# TC264D.net
KiCad netlist of a schematic drawn in EasyEDA Pro
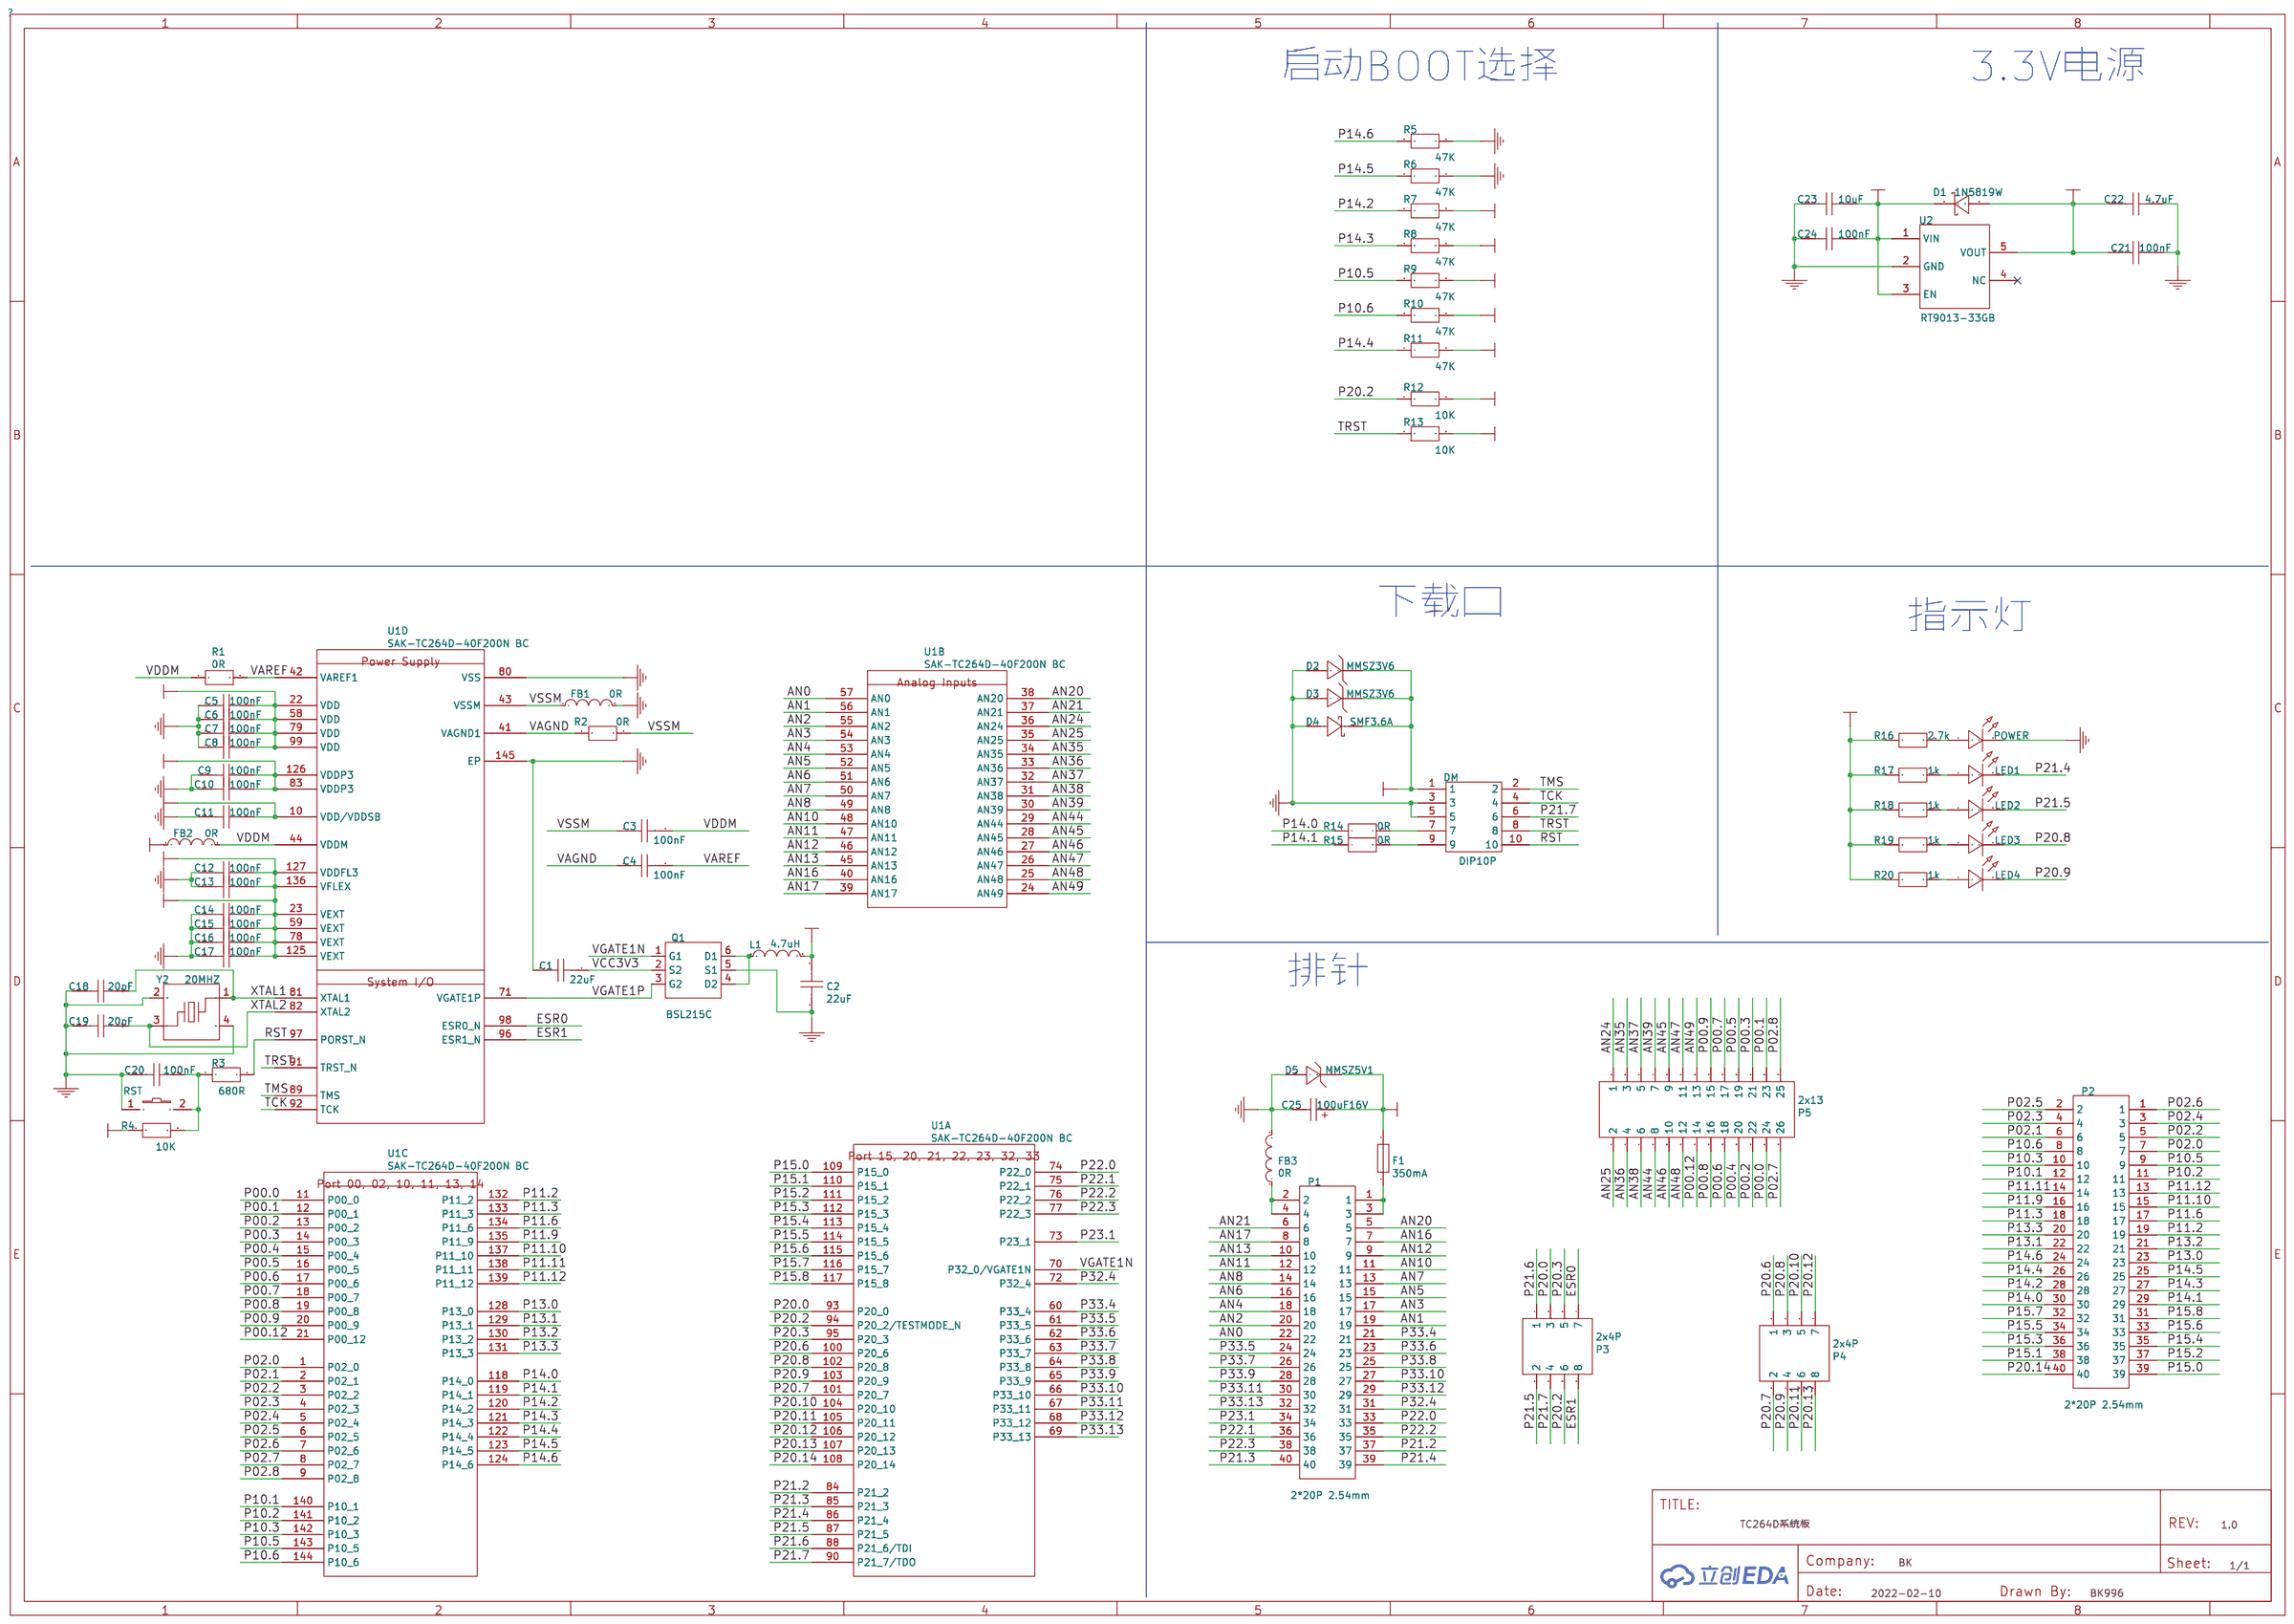
[diagram p0: schematic sheet]

(export (version "E")
  (design (tool "Eeschema 10.0.6"))
  (components
    (comp (ref "C1")
      (value "22uF")
      (footprint "easyedapro:C0603")
      (libsource (lib "easyedapro") (part "22uF"))
    )
    (comp (ref "C2")
      (value "22uF")
      (footprint "easyedapro:C0603")
      (libsource (lib "easyedapro") (part "22uF"))
    )
    (comp (ref "C3")
      (value "100nF")
      (footprint "easyedapro:C0603")
      (libsource (lib "easyedapro") (part "100nF"))
    )
    (comp (ref "C4")
      (value "100nF")
      (footprint "easyedapro:C0603")
      (libsource (lib "easyedapro") (part "100nF"))
    )
    (comp (ref "C5")
      (value "100nF")
      (footprint "easyedapro:C0603")
      (libsource (lib "easyedapro") (part "100nF"))
    )
    (comp (ref "C6")
      (value "100nF")
      (footprint "easyedapro:C0603")
      (libsource (lib "easyedapro") (part "100nF"))
    )
    (comp (ref "C7")
      (value "100nF")
      (footprint "easyedapro:C0603")
      (libsource (lib "easyedapro") (part "100nF"))
    )
    (comp (ref "C8")
      (value "100nF")
      (footprint "easyedapro:C0603")
      (libsource (lib "easyedapro") (part "100nF"))
    )
    (comp (ref "C9")
      (value "100nF")
      (footprint "easyedapro:C0603")
      (libsource (lib "easyedapro") (part "100nF"))
    )
    (comp (ref "C10")
      (value "100nF")
      (footprint "easyedapro:C0603")
      (libsource (lib "easyedapro") (part "100nF"))
    )
    (comp (ref "C11")
      (value "100nF")
      (footprint "easyedapro:C0603")
      (libsource (lib "easyedapro") (part "100nF"))
    )
    (comp (ref "C12")
      (value "100nF")
      (footprint "easyedapro:C0603")
      (libsource (lib "easyedapro") (part "100nF"))
    )
    (comp (ref "C13")
      (value "100nF")
      (footprint "easyedapro:C0603")
      (libsource (lib "easyedapro") (part "100nF"))
    )
    (comp (ref "C14")
      (value "100nF")
      (footprint "easyedapro:C0603")
      (libsource (lib "easyedapro") (part "100nF"))
    )
    (comp (ref "C15")
      (value "100nF")
      (footprint "easyedapro:C0603")
      (libsource (lib "easyedapro") (part "100nF"))
    )
    (comp (ref "C16")
      (value "100nF")
      (footprint "easyedapro:C0603")
      (libsource (lib "easyedapro") (part "100nF"))
    )
    (comp (ref "C17")
      (value "100nF")
      (footprint "easyedapro:C0603")
      (libsource (lib "easyedapro") (part "100nF"))
    )
    (comp (ref "C18")
      (value "20pF")
      (footprint "easyedapro:C0603")
      (libsource (lib "easyedapro") (part "20pF"))
    )
    (comp (ref "C19")
      (value "20pF")
      (footprint "easyedapro:C0603")
      (libsource (lib "easyedapro") (part "20pF"))
    )
    (comp (ref "C20")
      (value "100nF")
      (footprint "easyedapro:C0603")
      (libsource (lib "easyedapro") (part "100nF"))
    )
    (comp (ref "C21")
      (value "100nF")
      (footprint "easyedapro:C0603")
      (libsource (lib "easyedapro") (part "100nF"))
    )
    (comp (ref "C22")
      (value "4.7uF")
      (footprint "easyedapro:C0603")
      (libsource (lib "easyedapro") (part "4.7uF"))
    )
    (comp (ref "C23")
      (value "10uF")
      (footprint "easyedapro:C0603")
      (libsource (lib "easyedapro") (part "10uF"))
    )
    (comp (ref "C24")
      (value "100nF")
      (footprint "easyedapro:C0603")
      (libsource (lib "easyedapro") (part "100nF"))
    )
    (comp (ref "C25")
      (value "100uF16V")
      (footprint "easyedapro:CAP-SMD_L7.3-W4.3-R-RD")
      (fields (field (name "Manufacturer Part") "CA45-D-16V-100UF-K") (field (name "Manufacturer") "CEC"))
      (libsource (lib "easyedapro") (part "100uF16V"))
    )
    (comp (ref "D1")
      (value "1N5819W")
      (footprint "easyedapro:SOD-123F_L2.8-W1.8-LS3.7-RD")
      (fields (field (name "Manufacturer") "Shandong Jingdao Microelectronics"))
      (libsource (lib "easyedapro") (part "1N5819W"))
    )
    (comp (ref "D2")
      (value "MMSZ3V6")
      (footprint "easyedapro:SOD-123_L2.6-W1.6-LS3.5-RD")
      (fields (field (name "Manufacturer Part") "MMSZ3V6CW") (field (name "Manufacturer") "Tak Cheong"))
      (libsource (lib "easyedapro") (part "MMSZ3V6"))
    )
    (comp (ref "D3")
      (value "MMSZ3V6")
      (footprint "easyedapro:SOD-123_L2.6-W1.6-LS3.5-RD")
      (fields (field (name "Manufacturer Part") "MMSZ3V6CW") (field (name "Manufacturer") "Tak Cheong"))
      (libsource (lib "easyedapro") (part "MMSZ3V6"))
    )
    (comp (ref "D4")
      (value "SMF3.6A")
      (footprint "easyedapro:SMF_L2.8-W1.8-LS3.7-FD-1")
      (fields (field (name "Manufacturer Part") "SMF8V5A-E3-18") (field (name "Manufacturer") "VISHAY(威世)"))
      (libsource (lib "easyedapro") (part "SMF3.6A"))
    )
    (comp (ref "D5")
      (value "MMSZ5V1")
      (footprint "easyedapro:SOD-123_L2.7-W1.6-LS3.7-RD")
      (fields (field (name "Manufacturer Part") "MMSZ5V1T1G") (field (name "Manufacturer") "ON Semicon"))
      (libsource (lib "easyedapro") (part "MMSZ5V1"))
    )
    (comp (ref "DM")
      (value "DIP10P")
      (footprint "easyedapro:DIP-2X5P-2.54MM-JN")
      (fields (field (name "Manufacturer Part") "Z-2310118161010") (field (name "Manufacturer") "ZHENGLING"))
      (libsource (lib "easyedapro") (part "DIP10P"))
    )
    (comp (ref "F1")
      (value "350mA")
      (footprint "easyedapro:F1206")
      (fields
        (field (name "Manufacturer Part") "FSMD012-1206-R")
        (field (name "Manufacturer") "Fuzetec Tech")
      )
      (libsource (lib "easyedapro") (part "350mA"))
    )
    (comp (ref "FB1")
      (value "0R")
      (footprint "easyedapro:FB0603")
      (fields (field (name "Manufacturer Part") "PZ2012U121-1R0TF") (field (name "Manufacturer") "Sunlord"))
      (libsource (lib "easyedapro") (part "0R"))
    )
    (comp (ref "FB2")
      (value "0R")
      (footprint "easyedapro:FB0603")
      (fields (field (name "Manufacturer Part") "PZ2012U121-1R0TF") (field (name "Manufacturer") "Sunlord"))
      (libsource (lib "easyedapro") (part "0R"))
    )
    (comp (ref "FB3")
      (value "0R")
      (footprint "easyedapro:FB0603")
      (fields (field (name "Manufacturer Part") "PZ2012U121-1R0TF") (field (name "Manufacturer") "Sunlord"))
      (libsource (lib "easyedapro") (part "0R"))
    )
    (comp (ref "L1")
      (value "4.7uH")
      (footprint "easyedapro:IND-SMD_L7.3-W6.6_MHCI06030")
      (fields (field (name "Manufacturer Part") "MHCI06030-4R7M-R8") (field (name "Manufacturer") "Chilisin"))
      (libsource (lib "easyedapro") (part "4.7uH"))
    )
    (comp (ref "LED1")
      (value "LED-0603_G")
      (footprint "easyedapro:LED0603_GREEN")
      (fields
        (field (name "Manufacturer Part") "19-217/GHC-YR1S2/3T")
        (field (name "Manufacturer") "EVERLIGHT(台湾亿光)")
      )
      (libsource (lib "easyedapro") (part "LED-0603_G"))
    )
    (comp (ref "LED2")
      (value "LED-0603_G")
      (footprint "easyedapro:LED0603_GREEN")
      (fields
        (field (name "Manufacturer Part") "19-217/GHC-YR1S2/3T")
        (field (name "Manufacturer") "EVERLIGHT(台湾亿光)")
      )
      (libsource (lib "easyedapro") (part "LED-0603_G"))
    )
    (comp (ref "LED3")
      (value "LED-0603_G")
      (footprint "easyedapro:LED0603_GREEN")
      (fields
        (field (name "Manufacturer Part") "19-217/GHC-YR1S2/3T")
        (field (name "Manufacturer") "EVERLIGHT(台湾亿光)")
      )
      (libsource (lib "easyedapro") (part "LED-0603_G"))
    )
    (comp (ref "LED4")
      (value "LED-0603_G")
      (footprint "easyedapro:LED0603_GREEN")
      (fields
        (field (name "Manufacturer Part") "19-217/GHC-YR1S2/3T")
        (field (name "Manufacturer") "EVERLIGHT(台湾亿光)")
      )
      (libsource (lib "easyedapro") (part "LED-0603_G"))
    )
    (comp (ref "P1")
      (value "2*20P 2.54mm")
      (footprint "easyedapro:HDR-TH_40P-P2.54-V-F-R2-C20-S2.54")
      (fields (field (name "Manufacturer") "Shenzhen Cankemeng"))
      (libsource (lib "easyedapro") (part "2*20P 2.54mm"))
    )
    (comp (ref "P2")
      (value "2*20P 2.54mm")
      (footprint "easyedapro:HDR-TH_40P-P2.54-V-F-R2-C20-S2.54")
      (fields (field (name "Manufacturer") "Shenzhen Cankemeng"))
      (libsource (lib "easyedapro") (part "2*20P 2.54mm"))
    )
    (comp (ref "P3")
      (value "2x4P")
      (footprint "easyedapro:HDR-TH_8P-P2.54-V-M-R2-C4-S2.54")
      (fields (field (name "Manufacturer Part") "Header2X4P 2.54mm") (field (name "Manufacturer") "ReliaPro"))
      (libsource (lib "easyedapro") (part "2x4P"))
    )
    (comp (ref "P4")
      (value "2x4P")
      (footprint "easyedapro:HDR-TH_8P-P2.54-V-M-R2-C4-S2.54")
      (fields (field (name "Manufacturer Part") "Header2X4P 2.54mm") (field (name "Manufacturer") "ReliaPro"))
      (libsource (lib "easyedapro") (part "2x4P"))
    )
    (comp (ref "P5")
      (value "2x13")
      (footprint "easyedapro:HDR-TH_26P-P2.54-V-F-R2-C13-S2.54-1")
      (fields
        (field (name "Manufacturer Part") "2×13Female header Straight line")
        (field (name "Manufacturer") "BOOMELE")
      )
      (libsource (lib "easyedapro") (part "2x13"))
    )
    (comp (ref "POWER")
      (value "LED-0603_R")
      (footprint "easyedapro:LED0603_RED")
      (fields
        (field (name "Manufacturer Part") "19-217/R6C-AL1M2VY/3T")
        (field (name "Manufacturer") "EVERLIGHT(台湾亿光)")
      )
      (libsource (lib "easyedapro") (part "LED-0603_R"))
    )
    (comp (ref "Q1")
      (value "BSL215C")
      (footprint "easyedapro:TSOP-6_L3.0-W1.5-P0.95-LS2.8-BL")
      (fields (field (name "Manufacturer Part") "BSL215CH6327XTSA1") (field (name "Manufacturer") "Infineon"))
      (libsource (lib "easyedapro") (part "BSL215C"))
    )
    (comp (ref "R1") (value "0R") (footprint "easyedapro:R0805") (libsource (lib "") (part "0R_1")))
    (comp (ref "R2") (value "0R") (footprint "easyedapro:R0805") (libsource (lib "") (part "0R_1")))
    (comp (ref "R3")
      (value "680R")
      (footprint "easyedapro:R0603")
      (libsource (lib "easyedapro") (part "680R"))
    )
    (comp (ref "R4") (value "10K") (footprint "easyedapro:R0603") (libsource (lib "easyedapro") (part "10K")))
    (comp (ref "R5") (value "47K") (footprint "easyedapro:R0603") (libsource (lib "easyedapro") (part "47K")))
    (comp (ref "R6") (value "47K") (footprint "easyedapro:R0603") (libsource (lib "easyedapro") (part "47K")))
    (comp (ref "R7") (value "47K") (footprint "easyedapro:R0603") (libsource (lib "easyedapro") (part "47K")))
    (comp (ref "R8") (value "47K") (footprint "easyedapro:R0603") (libsource (lib "easyedapro") (part "47K")))
    (comp (ref "R9") (value "47K") (footprint "easyedapro:R0603") (libsource (lib "easyedapro") (part "47K")))
    (comp (ref "R10")
      (value "47K")
      (footprint "easyedapro:R0603")
      (libsource (lib "easyedapro") (part "47K"))
    )
    (comp (ref "R11")
      (value "47K")
      (footprint "easyedapro:R0603")
      (libsource (lib "easyedapro") (part "47K"))
    )
    (comp (ref "R12")
      (value "10K")
      (footprint "easyedapro:R0603")
      (libsource (lib "easyedapro") (part "10K"))
    )
    (comp (ref "R13")
      (value "10K")
      (footprint "easyedapro:R0603")
      (libsource (lib "easyedapro") (part "10K"))
    )
    (comp (ref "R14") (value "0R") (footprint "easyedapro:R0805") (libsource (lib "") (part "0R_1")))
    (comp (ref "R15") (value "0R") (footprint "easyedapro:R0805") (libsource (lib "") (part "0R_1")))
    (comp (ref "R16")
      (value "2.7k")
      (footprint "easyedapro:R0603")
      (libsource (lib "easyedapro") (part "2.7k"))
    )
    (comp (ref "R17") (value "1k") (footprint "easyedapro:R0603") (libsource (lib "easyedapro") (part "1k")))
    (comp (ref "R18") (value "1k") (footprint "easyedapro:R0603") (libsource (lib "easyedapro") (part "1k")))
    (comp (ref "R19") (value "1k") (footprint "easyedapro:R0603") (libsource (lib "easyedapro") (part "1k")))
    (comp (ref "R20") (value "1k") (footprint "easyedapro:R0603") (libsource (lib "easyedapro") (part "1k")))
    (comp (ref "RST")
      (value "K2-3.6×6.1_SMD")
      (footprint "easyedapro:3*6*2.5MM轻触开关")
      (fields (field (name "Manufacturer Part") "K2-1107ST-A4SW-06"))
      (libsource (lib "easyedapro") (part "K2-3.6×6.1_SMD"))
    )
    (comp (ref "U1")
      (value "SAK-TC264D-40F200N BC")
      (footprint "easyedapro:QFP50P2200X2200X160-145N-1")
      (fields (field (name "Manufacturer") "Infineon Technologies"))
      (libsource (lib "easyedapro") (part "SAK-TC264D-40F200N BC"))
    )
    (comp (ref "U2")
      (value "RT9013-33GB")
      (footprint "easyedapro:SOT-23-5_L3.0-W1.7-P0.95-LS2.8-BR")
      (fields (field (name "Manufacturer") "RICHTEK"))
      (libsource (lib "easyedapro") (part "RT9013-33GB"))
    )
    (comp (ref "Y2")
      (value "20MHZ")
      (footprint "easyedapro:CRYSTAL-SMD_4P-L3.2-W2.5-BL")
      (fields (field (name "Manufacturer Part") "smd-3225-8Mhz"))
      (libsource (lib "easyedapro") (part "20MHZ"))
    )
  )
  (nets
    (net (code "1") (name "/AN0") (class "Default")
      (node (ref "P1") (pin "22") (pinfunction "22_22") (pintype "unspecified"))
      (node (ref "U1") (pin "57") (pinfunction "AN0_57") (pintype "input"))
    )
    (net (code "2") (name "/AN1") (class "Default")
      (node (ref "P1") (pin "19") (pinfunction "19_19") (pintype "unspecified"))
      (node (ref "U1") (pin "56") (pinfunction "AN1_56") (pintype "input"))
    )
    (net (code "3") (name "/AN2") (class "Default")
      (node (ref "P1") (pin "20") (pinfunction "20_20") (pintype "unspecified"))
      (node (ref "U1") (pin "55") (pinfunction "AN2_55") (pintype "input"))
    )
    (net (code "4") (name "/AN3") (class "Default")
      (node (ref "P1") (pin "17") (pinfunction "17_17") (pintype "unspecified"))
      (node (ref "U1") (pin "54") (pinfunction "AN3_54") (pintype "input"))
    )
    (net (code "5") (name "/AN4") (class "Default")
      (node (ref "P1") (pin "18") (pinfunction "18_18") (pintype "unspecified"))
      (node (ref "U1") (pin "53") (pinfunction "AN4_53") (pintype "input"))
    )
    (net (code "6") (name "/AN5") (class "Default")
      (node (ref "P1") (pin "15") (pinfunction "15_15") (pintype "unspecified"))
      (node (ref "U1") (pin "52") (pinfunction "AN5_52") (pintype "input"))
    )
    (net (code "7") (name "/AN6") (class "Default")
      (node (ref "P1") (pin "16") (pinfunction "16_16") (pintype "unspecified"))
      (node (ref "U1") (pin "51") (pinfunction "AN6_51") (pintype "input"))
    )
    (net (code "8") (name "/AN7") (class "Default")
      (node (ref "P1") (pin "13") (pinfunction "13_13") (pintype "unspecified"))
      (node (ref "U1") (pin "50") (pinfunction "AN7_50") (pintype "input"))
    )
    (net (code "9") (name "/AN8") (class "Default")
      (node (ref "P1") (pin "14") (pinfunction "14_14") (pintype "unspecified"))
      (node (ref "U1") (pin "49") (pinfunction "AN8_49") (pintype "input"))
    )
    (net (code "10") (name "/AN10") (class "Default")
      (node (ref "P1") (pin "11") (pinfunction "11_11") (pintype "unspecified"))
      (node (ref "U1") (pin "48") (pinfunction "AN10_48") (pintype "input"))
    )
    (net (code "11") (name "/AN11") (class "Default")
      (node (ref "P1") (pin "12") (pinfunction "12_12") (pintype "unspecified"))
      (node (ref "U1") (pin "47") (pinfunction "AN11_47") (pintype "input"))
    )
    (net (code "12") (name "/AN12") (class "Default")
      (node (ref "P1") (pin "9") (pinfunction "9_9") (pintype "unspecified"))
      (node (ref "U1") (pin "46") (pinfunction "AN12_46") (pintype "input"))
    )
    (net (code "13") (name "/AN13") (class "Default")
      (node (ref "P1") (pin "10") (pinfunction "10_10") (pintype "unspecified"))
      (node (ref "U1") (pin "45") (pinfunction "AN13_45") (pintype "input"))
    )
    (net (code "14") (name "/AN16") (class "Default")
      (node (ref "P1") (pin "7") (pinfunction "7_7") (pintype "unspecified"))
      (node (ref "U1") (pin "40") (pinfunction "AN16_40") (pintype "input"))
    )
    (net (code "15") (name "/AN17") (class "Default")
      (node (ref "P1") (pin "8") (pinfunction "8_8") (pintype "unspecified"))
      (node (ref "U1") (pin "39") (pinfunction "AN17_39") (pintype "input"))
    )
    (net (code "16") (name "/AN20") (class "Default")
      (node (ref "P1") (pin "5") (pinfunction "5_5") (pintype "unspecified"))
      (node (ref "U1") (pin "38") (pinfunction "AN20_38") (pintype "input"))
    )
    (net (code "17") (name "/AN21") (class "Default")
      (node (ref "P1") (pin "6") (pinfunction "6_6") (pintype "unspecified"))
      (node (ref "U1") (pin "37") (pinfunction "AN21_37") (pintype "input"))
    )
    (net (code "18") (name "/AN24") (class "Default")
      (node (ref "P5") (pin "1") (pinfunction "1_1") (pintype "input"))
      (node (ref "U1") (pin "36") (pinfunction "AN24_36") (pintype "input"))
    )
    (net (code "19") (name "/AN25") (class "Default")
      (node (ref "P5") (pin "2") (pinfunction "2_2") (pintype "input"))
      (node (ref "U1") (pin "35") (pinfunction "AN25_35") (pintype "input"))
    )
    (net (code "20") (name "/AN35") (class "Default")
      (node (ref "P5") (pin "3") (pinfunction "3_3") (pintype "input"))
      (node (ref "U1") (pin "34") (pinfunction "AN35_34") (pintype "input"))
    )
    (net (code "21") (name "/AN36") (class "Default")
      (node (ref "P5") (pin "4") (pinfunction "4_4") (pintype "input"))
      (node (ref "U1") (pin "33") (pinfunction "AN36_33") (pintype "input"))
    )
    (net (code "22") (name "/AN37") (class "Default")
      (node (ref "P5") (pin "5") (pinfunction "5_5") (pintype "input"))
      (node (ref "U1") (pin "32") (pinfunction "AN37_32") (pintype "input"))
    )
    (net (code "23") (name "/AN38") (class "Default")
      (node (ref "P5") (pin "6") (pinfunction "6_6") (pintype "input"))
      (node (ref "U1") (pin "31") (pinfunction "AN38_31") (pintype "input"))
    )
    (net (code "24") (name "/AN39") (class "Default")
      (node (ref "P5") (pin "7") (pinfunction "7_7") (pintype "input"))
      (node (ref "U1") (pin "30") (pinfunction "AN39_30") (pintype "input"))
    )
    (net (code "25") (name "/AN44") (class "Default")
      (node (ref "P5") (pin "8") (pinfunction "8_8") (pintype "input"))
      (node (ref "U1") (pin "29") (pinfunction "AN44_29") (pintype "input"))
    )
    (net (code "26") (name "/AN45") (class "Default")
      (node (ref "P5") (pin "9") (pinfunction "9_9") (pintype "input"))
      (node (ref "U1") (pin "28") (pinfunction "AN45_28") (pintype "input"))
    )
    (net (code "27") (name "/AN46") (class "Default")
      (node (ref "P5") (pin "10") (pinfunction "10_10") (pintype "input"))
      (node (ref "U1") (pin "27") (pinfunction "AN46_27") (pintype "input"))
    )
    (net (code "28") (name "/AN47") (class "Default")
      (node (ref "P5") (pin "11") (pinfunction "11_11") (pintype "input"))
      (node (ref "U1") (pin "26") (pinfunction "AN47_26") (pintype "input"))
    )
    (net (code "29") (name "/AN48") (class "Default")
      (node (ref "P5") (pin "12") (pinfunction "12_12") (pintype "input"))
      (node (ref "U1") (pin "25") (pinfunction "AN48_25") (pintype "input"))
    )
    (net (code "30") (name "/AN49") (class "Default")
      (node (ref "P5") (pin "13") (pinfunction "13_13") (pintype "input"))
      (node (ref "U1") (pin "24") (pinfunction "AN49_24") (pintype "input"))
    )
    (net (code "31") (name "/ESR0") (class "Default")
      (node (ref "P3") (pin "7") (pinfunction "7_7") (pintype "input"))
      (node (ref "U1") (pin "98") (pinfunction "ESR0_N_98") (pintype "bidirectional"))
    )
    (net (code "32") (name "/ESR1") (class "Default")
      (node (ref "P3") (pin "8") (pinfunction "8_8") (pintype "input"))
      (node (ref "U1") (pin "96") (pinfunction "ESR1_N_96") (pintype "bidirectional"))
    )
    (net (code "33") (name "/P00.0") (class "Default")
      (node (ref "P5") (pin "24") (pinfunction "24_24") (pintype "input"))
      (node (ref "U1") (pin "11") (pinfunction "P00_0_11") (pintype "bidirectional"))
    )
    (net (code "34") (name "/P00.1") (class "Default")
      (node (ref "P5") (pin "23") (pinfunction "23_23") (pintype "input"))
      (node (ref "U1") (pin "12") (pinfunction "P00_1_12") (pintype "bidirectional"))
    )
    (net (code "35") (name "/P00.2") (class "Default")
      (node (ref "P5") (pin "22") (pinfunction "22_22") (pintype "input"))
      (node (ref "U1") (pin "13") (pinfunction "P00_2_13") (pintype "bidirectional"))
    )
    (net (code "36") (name "/P00.3") (class "Default")
      (node (ref "P5") (pin "21") (pinfunction "21_21") (pintype "input"))
      (node (ref "U1") (pin "14") (pinfunction "P00_3_14") (pintype "bidirectional"))
    )
    (net (code "37") (name "/P00.4") (class "Default")
      (node (ref "P5") (pin "20") (pinfunction "20_20") (pintype "input"))
      (node (ref "U1") (pin "15") (pinfunction "P00_4_15") (pintype "bidirectional"))
    )
    (net (code "38") (name "/P00.5") (class "Default")
      (node (ref "P5") (pin "19") (pinfunction "19_19") (pintype "input"))
      (node (ref "U1") (pin "16") (pinfunction "P00_5_16") (pintype "bidirectional"))
    )
    (net (code "39") (name "/P00.6") (class "Default")
      (node (ref "P5") (pin "18") (pinfunction "18_18") (pintype "input"))
      (node (ref "U1") (pin "17") (pinfunction "P00_6_17") (pintype "bidirectional"))
    )
    (net (code "40") (name "/P00.7") (class "Default")
      (node (ref "P5") (pin "17") (pinfunction "17_17") (pintype "input"))
      (node (ref "U1") (pin "18") (pinfunction "P00_7_18") (pintype "bidirectional"))
    )
    (net (code "41") (name "/P00.8") (class "Default")
      (node (ref "P5") (pin "16") (pinfunction "16_16") (pintype "input"))
      (node (ref "U1") (pin "19") (pinfunction "P00_8_19") (pintype "bidirectional"))
    )
    (net (code "42") (name "/P00.9") (class "Default")
      (node (ref "P5") (pin "15") (pinfunction "15_15") (pintype "input"))
      (node (ref "U1") (pin "20") (pinfunction "P00_9_20") (pintype "bidirectional"))
    )
    (net (code "43") (name "/P00.12") (class "Default")
      (node (ref "P5") (pin "14") (pinfunction "14_14") (pintype "input"))
      (node (ref "U1") (pin "21") (pinfunction "P00_12_21") (pintype "bidirectional"))
    )
    (net (code "44") (name "/P02.0") (class "Default")
      (node (ref "P2") (pin "7") (pinfunction "7_7") (pintype "unspecified"))
      (node (ref "U1") (pin "1") (pinfunction "P02_0_1") (pintype "bidirectional"))
    )
    (net (code "45") (name "/P02.1") (class "Default")
      (node (ref "P2") (pin "6") (pinfunction "6_6") (pintype "unspecified"))
      (node (ref "U1") (pin "2") (pinfunction "P02_1_2") (pintype "bidirectional"))
    )
    (net (code "46") (name "/P02.2") (class "Default")
      (node (ref "P2") (pin "5") (pinfunction "5_5") (pintype "unspecified"))
      (node (ref "U1") (pin "3") (pinfunction "P02_2_3") (pintype "bidirectional"))
    )
    (net (code "47") (name "/P02.3") (class "Default")
      (node (ref "P2") (pin "4") (pinfunction "4_4") (pintype "unspecified"))
      (node (ref "U1") (pin "4") (pinfunction "P02_3_4") (pintype "bidirectional"))
    )
    (net (code "48") (name "/P02.4") (class "Default")
      (node (ref "P2") (pin "3") (pinfunction "3_3") (pintype "unspecified"))
      (node (ref "U1") (pin "5") (pinfunction "P02_4_5") (pintype "bidirectional"))
    )
    (net (code "49") (name "/P02.5") (class "Default")
      (node (ref "P2") (pin "2") (pinfunction "2_2") (pintype "unspecified"))
      (node (ref "U1") (pin "6") (pinfunction "P02_5_6") (pintype "bidirectional"))
    )
    (net (code "50") (name "/P02.6") (class "Default")
      (node (ref "P2") (pin "1") (pinfunction "1_1") (pintype "unspecified"))
      (node (ref "U1") (pin "7") (pinfunction "P02_6_7") (pintype "bidirectional"))
    )
    (net (code "51") (name "/P02.7") (class "Default")
      (node (ref "P5") (pin "26") (pinfunction "26_26") (pintype "input"))
      (node (ref "U1") (pin "8") (pinfunction "P02_7_8") (pintype "bidirectional"))
    )
    (net (code "52") (name "/P02.8") (class "Default")
      (node (ref "P5") (pin "25") (pinfunction "25_25") (pintype "input"))
      (node (ref "U1") (pin "9") (pinfunction "P02_8_9") (pintype "bidirectional"))
    )
    (net (code "53") (name "/P10.1") (class "Default")
      (node (ref "P2") (pin "12") (pinfunction "12_12") (pintype "unspecified"))
      (node (ref "U1") (pin "140") (pinfunction "P10_1_140") (pintype "bidirectional"))
    )
    (net (code "54") (name "/P10.2") (class "Default")
      (node (ref "P2") (pin "11") (pinfunction "11_11") (pintype "unspecified"))
      (node (ref "U1") (pin "141") (pinfunction "P10_2_141") (pintype "bidirectional"))
    )
    (net (code "55") (name "/P10.3") (class "Default")
      (node (ref "P2") (pin "10") (pinfunction "10_10") (pintype "unspecified"))
      (node (ref "U1") (pin "142") (pinfunction "P10_3_142") (pintype "bidirectional"))
    )
    (net (code "56") (name "/P10.5") (class "Default")
      (node (ref "P2") (pin "9") (pinfunction "9_9") (pintype "unspecified"))
      (node (ref "R9") (pin "1") (pinfunction "1_1") (pintype "unspecified"))
      (node (ref "U1") (pin "143") (pinfunction "P10_5_143") (pintype "bidirectional"))
    )
    (net (code "57") (name "/P10.6") (class "Default")
      (node (ref "P2") (pin "8") (pinfunction "8_8") (pintype "unspecified"))
      (node (ref "R10") (pin "1") (pinfunction "1_1") (pintype "unspecified"))
      (node (ref "U1") (pin "144") (pinfunction "P10_6_144") (pintype "bidirectional"))
    )
    (net (code "58") (name "/P11.2") (class "Default")
      (node (ref "P2") (pin "19") (pinfunction "19_19") (pintype "unspecified"))
      (node (ref "U1") (pin "132") (pinfunction "P11_2_132") (pintype "bidirectional"))
    )
    (net (code "59") (name "/P11.3") (class "Default")
      (node (ref "P2") (pin "18") (pinfunction "18_18") (pintype "unspecified"))
      (node (ref "U1") (pin "133") (pinfunction "P11_3_133") (pintype "bidirectional"))
    )
    (net (code "60") (name "/P11.6") (class "Default")
      (node (ref "P2") (pin "17") (pinfunction "17_17") (pintype "unspecified"))
      (node (ref "U1") (pin "134") (pinfunction "P11_6_134") (pintype "bidirectional"))
    )
    (net (code "61") (name "/P11.9") (class "Default")
      (node (ref "P2") (pin "16") (pinfunction "16_16") (pintype "unspecified"))
      (node (ref "U1") (pin "135") (pinfunction "P11_9_135") (pintype "bidirectional"))
    )
    (net (code "62") (name "/P11.10") (class "Default")
      (node (ref "P2") (pin "15") (pinfunction "15_15") (pintype "unspecified"))
      (node (ref "U1") (pin "137") (pinfunction "P11_10_137") (pintype "bidirectional"))
    )
    (net (code "63") (name "/P11.11") (class "Default")
      (node (ref "P2") (pin "14") (pinfunction "14_14") (pintype "unspecified"))
      (node (ref "U1") (pin "138") (pinfunction "P11_11_138") (pintype "bidirectional"))
    )
    (net (code "64") (name "/P11.12") (class "Default")
      (node (ref "P2") (pin "13") (pinfunction "13_13") (pintype "unspecified"))
      (node (ref "U1") (pin "139") (pinfunction "P11_12_139") (pintype "bidirectional"))
    )
    (net (code "65") (name "/P13.0") (class "Default")
      (node (ref "P2") (pin "23") (pinfunction "23_23") (pintype "unspecified"))
      (node (ref "U1") (pin "128") (pinfunction "P13_0_128") (pintype "bidirectional"))
    )
    (net (code "66") (name "/P13.1") (class "Default")
      (node (ref "P2") (pin "22") (pinfunction "22_22") (pintype "unspecified"))
      (node (ref "U1") (pin "129") (pinfunction "P13_1_129") (pintype "bidirectional"))
    )
    (net (code "67") (name "/P13.2") (class "Default")
      (node (ref "P2") (pin "21") (pinfunction "21_21") (pintype "unspecified"))
      (node (ref "U1") (pin "130") (pinfunction "P13_2_130") (pintype "bidirectional"))
    )
    (net (code "68") (name "/P13.3") (class "Default")
      (node (ref "P2") (pin "20") (pinfunction "20_20") (pintype "unspecified"))
      (node (ref "U1") (pin "131") (pinfunction "P13_3_131") (pintype "bidirectional"))
    )
    (net (code "69") (name "/P14.0") (class "Default")
      (node (ref "P2") (pin "30") (pinfunction "30_30") (pintype "unspecified"))
      (node (ref "R14") (pin "1") (pinfunction "1_1") (pintype "unspecified"))
      (node (ref "U1") (pin "118") (pinfunction "P14_0_118") (pintype "bidirectional"))
    )
    (net (code "70") (name "/P14.1") (class "Default")
      (node (ref "P2") (pin "29") (pinfunction "29_29") (pintype "unspecified"))
      (node (ref "R15") (pin "1") (pinfunction "1_1") (pintype "unspecified"))
      (node (ref "U1") (pin "119") (pinfunction "P14_1_119") (pintype "bidirectional"))
    )
    (net (code "71") (name "/P14.2") (class "Default")
      (node (ref "P2") (pin "28") (pinfunction "28_28") (pintype "unspecified"))
      (node (ref "R7") (pin "1") (pinfunction "1_1") (pintype "unspecified"))
      (node (ref "U1") (pin "120") (pinfunction "P14_2_120") (pintype "bidirectional"))
    )
    (net (code "72") (name "/P14.3") (class "Default")
      (node (ref "P2") (pin "27") (pinfunction "27_27") (pintype "unspecified"))
      (node (ref "R8") (pin "1") (pinfunction "1_1") (pintype "unspecified"))
      (node (ref "U1") (pin "121") (pinfunction "P14_3_121") (pintype "bidirectional"))
    )
    (net (code "73") (name "/P14.4") (class "Default")
      (node (ref "P2") (pin "26") (pinfunction "26_26") (pintype "unspecified"))
      (node (ref "R11") (pin "1") (pinfunction "1_1") (pintype "unspecified"))
      (node (ref "U1") (pin "122") (pinfunction "P14_4_122") (pintype "bidirectional"))
    )
    (net (code "74") (name "/P14.5") (class "Default")
      (node (ref "P2") (pin "25") (pinfunction "25_25") (pintype "unspecified"))
      (node (ref "R6") (pin "1") (pinfunction "1_1") (pintype "unspecified"))
      (node (ref "U1") (pin "123") (pinfunction "P14_5_123") (pintype "bidirectional"))
    )
    (net (code "75") (name "/P14.6") (class "Default")
      (node (ref "P2") (pin "24") (pinfunction "24_24") (pintype "unspecified"))
      (node (ref "R5") (pin "1") (pinfunction "1_1") (pintype "unspecified"))
      (node (ref "U1") (pin "124") (pinfunction "P14_6_124") (pintype "bidirectional"))
    )
    (net (code "76") (name "/P15.0") (class "Default")
      (node (ref "P2") (pin "39") (pinfunction "39_39") (pintype "unspecified"))
      (node (ref "U1") (pin "109") (pinfunction "P15_0_109") (pintype "bidirectional"))
    )
    (net (code "77") (name "/P15.1") (class "Default")
      (node (ref "P2") (pin "38") (pinfunction "38_38") (pintype "unspecified"))
      (node (ref "U1") (pin "110") (pinfunction "P15_1_110") (pintype "bidirectional"))
    )
    (net (code "78") (name "/P15.2") (class "Default")
      (node (ref "P2") (pin "37") (pinfunction "37_37") (pintype "unspecified"))
      (node (ref "U1") (pin "111") (pinfunction "P15_2_111") (pintype "bidirectional"))
    )
    (net (code "79") (name "/P15.3") (class "Default")
      (node (ref "P2") (pin "36") (pinfunction "36_36") (pintype "unspecified"))
      (node (ref "U1") (pin "112") (pinfunction "P15_3_112") (pintype "bidirectional"))
    )
    (net (code "80") (name "/P15.4") (class "Default")
      (node (ref "P2") (pin "35") (pinfunction "35_35") (pintype "unspecified"))
      (node (ref "U1") (pin "113") (pinfunction "P15_4_113") (pintype "bidirectional"))
    )
    (net (code "81") (name "/P15.5") (class "Default")
      (node (ref "P2") (pin "34") (pinfunction "34_34") (pintype "unspecified"))
      (node (ref "U1") (pin "114") (pinfunction "P15_5_114") (pintype "bidirectional"))
    )
    (net (code "82") (name "/P15.6") (class "Default")
      (node (ref "P2") (pin "33") (pinfunction "33_33") (pintype "unspecified"))
      (node (ref "U1") (pin "115") (pinfunction "P15_6_115") (pintype "bidirectional"))
    )
    (net (code "83") (name "/P15.7") (class "Default")
      (node (ref "P2") (pin "32") (pinfunction "32_32") (pintype "unspecified"))
      (node (ref "U1") (pin "116") (pinfunction "P15_7_116") (pintype "bidirectional"))
    )
    (net (code "84") (name "/P15.8") (class "Default")
      (node (ref "P2") (pin "31") (pinfunction "31_31") (pintype "unspecified"))
      (node (ref "U1") (pin "117") (pinfunction "P15_8_117") (pintype "bidirectional"))
    )
    (net (code "85") (name "/P20.0") (class "Default")
      (node (ref "P3") (pin "3") (pinfunction "3_3") (pintype "input"))
      (node (ref "U1") (pin "93") (pinfunction "P20_0_93") (pintype "bidirectional"))
    )
    (net (code "86") (name "/P20.2") (class "Default")
      (node (ref "P3") (pin "6") (pinfunction "6_6") (pintype "input"))
      (node (ref "R12") (pin "1") (pinfunction "1_1") (pintype "unspecified"))
      (node (ref "U1") (pin "94") (pinfunction "P20_2/TESTMODE_N_94") (pintype "bidirectional"))
    )
    (net (code "87") (name "/P20.3") (class "Default")
      (node (ref "P3") (pin "5") (pinfunction "5_5") (pintype "input"))
      (node (ref "U1") (pin "95") (pinfunction "P20_3_95") (pintype "bidirectional"))
    )
    (net (code "88") (name "/P20.6") (class "Default")
      (node (ref "P4") (pin "1") (pinfunction "1_1") (pintype "input"))
      (node (ref "U1") (pin "100") (pinfunction "P20_6_100") (pintype "bidirectional"))
    )
    (net (code "89") (name "/P20.7") (class "Default")
      (node (ref "P4") (pin "2") (pinfunction "2_2") (pintype "input"))
      (node (ref "U1") (pin "101") (pinfunction "P20_7_101") (pintype "bidirectional"))
    )
    (net (code "90") (name "/P20.8") (class "Default")
      (node (ref "LED3") (pin "2") (pinfunction "2_2") (pintype "unspecified"))
      (node (ref "P4") (pin "3") (pinfunction "3_3") (pintype "input"))
      (node (ref "U1") (pin "102") (pinfunction "P20_8_102") (pintype "bidirectional"))
    )
    (net (code "91") (name "/P20.9") (class "Default")
      (node (ref "LED4") (pin "2") (pinfunction "2_2") (pintype "unspecified"))
      (node (ref "P4") (pin "4") (pinfunction "4_4") (pintype "input"))
      (node (ref "U1") (pin "103") (pinfunction "P20_9_103") (pintype "bidirectional"))
    )
    (net (code "92") (name "/P20.10") (class "Default")
      (node (ref "P4") (pin "5") (pinfunction "5_5") (pintype "input"))
      (node (ref "U1") (pin "104") (pinfunction "P20_10_104") (pintype "bidirectional"))
    )
    (net (code "93") (name "/P20.11") (class "Default")
      (node (ref "P4") (pin "6") (pinfunction "6_6") (pintype "input"))
      (node (ref "U1") (pin "105") (pinfunction "P20_11_105") (pintype "bidirectional"))
    )
    (net (code "94") (name "/P20.12") (class "Default")
      (node (ref "P4") (pin "7") (pinfunction "7_7") (pintype "input"))
      (node (ref "U1") (pin "106") (pinfunction "P20_12_106") (pintype "bidirectional"))
    )
    (net (code "95") (name "/P20.13") (class "Default")
      (node (ref "P4") (pin "8") (pinfunction "8_8") (pintype "input"))
      (node (ref "U1") (pin "107") (pinfunction "P20_13_107") (pintype "bidirectional"))
    )
    (net (code "96") (name "/P20.14") (class "Default")
      (node (ref "P2") (pin "40") (pinfunction "40_40") (pintype "unspecified"))
      (node (ref "U1") (pin "108") (pinfunction "P20_14_108") (pintype "bidirectional"))
    )
    (net (code "97") (name "/P21.2") (class "Default")
      (node (ref "P1") (pin "37") (pinfunction "37_37") (pintype "unspecified"))
      (node (ref "U1") (pin "84") (pinfunction "P21_2_84") (pintype "bidirectional"))
    )
    (net (code "98") (name "/P21.3") (class "Default")
      (node (ref "P1") (pin "40") (pinfunction "40_40") (pintype "unspecified"))
      (node (ref "U1") (pin "85") (pinfunction "P21_3_85") (pintype "bidirectional"))
    )
    (net (code "99") (name "/P21.4") (class "Default")
      (node (ref "LED1") (pin "2") (pinfunction "2_2") (pintype "unspecified"))
      (node (ref "P1") (pin "39") (pinfunction "39_39") (pintype "unspecified"))
      (node (ref "U1") (pin "86") (pinfunction "P21_4_86") (pintype "bidirectional"))
    )
    (net (code "100") (name "/P21.5") (class "Default")
      (node (ref "LED2") (pin "2") (pinfunction "2_2") (pintype "unspecified"))
      (node (ref "P3") (pin "2") (pinfunction "2_2") (pintype "input"))
      (node (ref "U1") (pin "87") (pinfunction "P21_5_87") (pintype "bidirectional"))
    )
    (net (code "101") (name "/P21.6") (class "Default")
      (node (ref "P3") (pin "1") (pinfunction "1_1") (pintype "input"))
      (node (ref "U1") (pin "88") (pinfunction "P21_6/TDI_88") (pintype "bidirectional"))
    )
    (net (code "102") (name "/P21.7") (class "Default")
      (node (ref "DM") (pin "6") (pinfunction "6_6") (pintype "unspecified"))
      (node (ref "P3") (pin "4") (pinfunction "4_4") (pintype "input"))
      (node (ref "U1") (pin "90") (pinfunction "P21_7/TDO_90") (pintype "bidirectional"))
    )
    (net (code "103") (name "/P22.0") (class "Default")
      (node (ref "P1") (pin "33") (pinfunction "33_33") (pintype "unspecified"))
      (node (ref "U1") (pin "74") (pinfunction "P22_0_74") (pintype "bidirectional"))
    )
    (net (code "104") (name "/P22.1") (class "Default")
      (node (ref "P1") (pin "36") (pinfunction "36_36") (pintype "unspecified"))
      (node (ref "U1") (pin "75") (pinfunction "P22_1_75") (pintype "bidirectional"))
    )
    (net (code "105") (name "/P22.2") (class "Default")
      (node (ref "P1") (pin "35") (pinfunction "35_35") (pintype "unspecified"))
      (node (ref "U1") (pin "76") (pinfunction "P22_2_76") (pintype "bidirectional"))
    )
    (net (code "106") (name "/P22.3") (class "Default")
      (node (ref "P1") (pin "38") (pinfunction "38_38") (pintype "unspecified"))
      (node (ref "U1") (pin "77") (pinfunction "P22_3_77") (pintype "bidirectional"))
    )
    (net (code "107") (name "/P23.1") (class "Default")
      (node (ref "P1") (pin "34") (pinfunction "34_34") (pintype "unspecified"))
      (node (ref "U1") (pin "73") (pinfunction "P23_1_73") (pintype "bidirectional"))
    )
    (net (code "108") (name "/P32.4") (class "Default")
      (node (ref "P1") (pin "31") (pinfunction "31_31") (pintype "unspecified"))
      (node (ref "U1") (pin "72") (pinfunction "P32_4_72") (pintype "bidirectional"))
    )
    (net (code "109") (name "/P33.4") (class "Default")
      (node (ref "P1") (pin "21") (pinfunction "21_21") (pintype "unspecified"))
      (node (ref "U1") (pin "60") (pinfunction "P33_4_60") (pintype "bidirectional"))
    )
    (net (code "110") (name "/P33.5") (class "Default")
      (node (ref "P1") (pin "24") (pinfunction "24_24") (pintype "unspecified"))
      (node (ref "U1") (pin "61") (pinfunction "P33_5_61") (pintype "bidirectional"))
    )
    (net (code "111") (name "/P33.6") (class "Default")
      (node (ref "P1") (pin "23") (pinfunction "23_23") (pintype "unspecified"))
      (node (ref "U1") (pin "62") (pinfunction "P33_6_62") (pintype "bidirectional"))
    )
    (net (code "112") (name "/P33.7") (class "Default")
      (node (ref "P1") (pin "26") (pinfunction "26_26") (pintype "unspecified"))
      (node (ref "U1") (pin "63") (pinfunction "P33_7_63") (pintype "bidirectional"))
    )
    (net (code "113") (name "/P33.8") (class "Default")
      (node (ref "P1") (pin "25") (pinfunction "25_25") (pintype "unspecified"))
      (node (ref "U1") (pin "64") (pinfunction "P33_8_64") (pintype "bidirectional"))
    )
    (net (code "114") (name "/P33.9") (class "Default")
      (node (ref "P1") (pin "28") (pinfunction "28_28") (pintype "unspecified"))
      (node (ref "U1") (pin "65") (pinfunction "P33_9_65") (pintype "bidirectional"))
    )
    (net (code "115") (name "/P33.10") (class "Default")
      (node (ref "P1") (pin "27") (pinfunction "27_27") (pintype "unspecified"))
      (node (ref "U1") (pin "66") (pinfunction "P33_10_66") (pintype "bidirectional"))
    )
    (net (code "116") (name "/P33.11") (class "Default")
      (node (ref "P1") (pin "30") (pinfunction "30_30") (pintype "unspecified"))
      (node (ref "U1") (pin "67") (pinfunction "P33_11_67") (pintype "bidirectional"))
    )
    (net (code "117") (name "/P33.12") (class "Default")
      (node (ref "P1") (pin "29") (pinfunction "29_29") (pintype "unspecified"))
      (node (ref "U1") (pin "68") (pinfunction "P33_12_68") (pintype "bidirectional"))
    )
    (net (code "118") (name "/P33.13") (class "Default")
      (node (ref "P1") (pin "32") (pinfunction "32_32") (pintype "unspecified"))
      (node (ref "U1") (pin "69") (pinfunction "P33_13_69") (pintype "bidirectional"))
    )
    (net (code "119") (name "/RST") (class "Default")
      (node (ref "DM") (pin "10") (pinfunction "10_10") (pintype "unspecified"))
      (node (ref "R3") (pin "2") (pinfunction "2_2") (pintype "unspecified"))
      (node (ref "U1") (pin "97") (pinfunction "PORST_N_97") (pintype "input"))
    )
    (net (code "120") (name "/TCK") (class "Default")
      (node (ref "DM") (pin "4") (pinfunction "4_4") (pintype "unspecified"))
      (node (ref "U1") (pin "92") (pinfunction "TCK_92") (pintype "input"))
    )
    (net (code "121") (name "/TMS") (class "Default")
      (node (ref "DM") (pin "2") (pinfunction "2_2") (pintype "unspecified"))
      (node (ref "U1") (pin "89") (pinfunction "TMS_89") (pintype "input"))
    )
    (net (code "122") (name "/TRST") (class "Default")
      (node (ref "DM") (pin "8") (pinfunction "8_8") (pintype "unspecified"))
      (node (ref "R13") (pin "1") (pinfunction "1_1") (pintype "unspecified"))
      (node (ref "U1") (pin "91") (pinfunction "TRST_N_91") (pintype "input"))
    )
    (net (code "123") (name "/VAGND") (class "Default")
      (node (ref "C4") (pin "1") (pinfunction "1_1") (pintype "unspecified"))
      (node (ref "R2") (pin "1") (pinfunction "1_1") (pintype "unspecified"))
      (node (ref "U1") (pin "41") (pinfunction "VAGND1_41") (pintype "unspecified"))
    )
    (net (code "124") (name "/VAREF") (class "Default")
      (node (ref "C4") (pin "2") (pinfunction "2_2") (pintype "unspecified"))
      (node (ref "R1") (pin "2") (pinfunction "2_2") (pintype "unspecified"))
      (node (ref "U1") (pin "42") (pinfunction "VAREF1_42") (pintype "unspecified"))
    )
    (net (code "125") (name "/VDDM") (class "Default")
      (node (ref "C3") (pin "2") (pinfunction "2_2") (pintype "unspecified"))
      (node (ref "FB2") (pin "2") (pinfunction "2_2") (pintype "unspecified"))
      (node (ref "R1") (pin "1") (pinfunction "1_1") (pintype "unspecified"))
      (node (ref "U1") (pin "44") (pinfunction "VDDM_44") (pintype "unspecified"))
    )
    (net (code "126") (name "/VGATE1N") (class "Default")
      (node (ref "Q1") (pin "1") (pinfunction "G1_1") (pintype "unspecified"))
      (node (ref "U1") (pin "70") (pinfunction "P32_0/VGATE1N_70") (pintype "bidirectional"))
    )
    (net (code "127") (name "/VGATE1P") (class "Default")
      (node (ref "Q1") (pin "3") (pinfunction "G2_3") (pintype "unspecified"))
      (node (ref "U1") (pin "71") (pinfunction "VGATE1P_71") (pintype "output"))
    )
    (net (code "128") (name "/VSSM") (class "Default")
      (node (ref "C3") (pin "1") (pinfunction "1_1") (pintype "unspecified"))
      (node (ref "FB1") (pin "1") (pinfunction "1_1") (pintype "unspecified"))
      (node (ref "R2") (pin "2") (pinfunction "2_2") (pintype "unspecified"))
      (node (ref "U1") (pin "43") (pinfunction "VSSM_43") (pintype "unspecified"))
    )
    (net (code "129") (name "/XTAL1") (class "Default")
      (node (ref "C18") (pin "2") (pinfunction "2_2") (pintype "unspecified"))
      (node (ref "U1") (pin "81") (pinfunction "XTAL1_81") (pintype "input"))
      (node (ref "Y2") (pin "1") (pinfunction "1_1") (pintype "input"))
    )
    (net (code "130") (name "/XTAL2") (class "Default")
      (node (ref "C19") (pin "2") (pinfunction "2_2") (pintype "unspecified"))
      (node (ref "U1") (pin "82") (pinfunction "XTAL2_82") (pintype "output"))
      (node (ref "Y2") (pin "3") (pinfunction "3_3") (pintype "input"))
    )
    (net (code "131") (name "GNDCORE") (class "Default")
      (node (ref "C1") (pin "1") (pinfunction "1_1") (pintype "unspecified"))
      (node (ref "C10") (pin "1") (pinfunction "1_1") (pintype "unspecified"))
      (node (ref "C11") (pin "1") (pinfunction "1_1") (pintype "unspecified"))
      (node (ref "C12") (pin "1") (pinfunction "1_1") (pintype "unspecified"))
      (node (ref "C13") (pin "1") (pinfunction "1_1") (pintype "unspecified"))
      (node (ref "C14") (pin "1") (pinfunction "1_1") (pintype "unspecified"))
      (node (ref "C15") (pin "1") (pinfunction "1_1") (pintype "unspecified"))
      (node (ref "C16") (pin "1") (pinfunction "1_1") (pintype "unspecified"))
      (node (ref "C17") (pin "1") (pinfunction "1_1") (pintype "unspecified"))
      (node (ref "C18") (pin "1") (pinfunction "1_1") (pintype "unspecified"))
      (node (ref "C19") (pin "1") (pinfunction "1_1") (pintype "unspecified"))
      (node (ref "C2") (pin "1") (pinfunction "1_1") (pintype "unspecified"))
      (node (ref "C20") (pin "1") (pinfunction "1_1") (pintype "unspecified"))
      (node (ref "C21") (pin "2") (pinfunction "2_2") (pintype "unspecified"))
      (node (ref "C22") (pin "2") (pinfunction "2_2") (pintype "unspecified"))
      (node (ref "C23") (pin "1") (pinfunction "1_1") (pintype "unspecified"))
      (node (ref "C24") (pin "1") (pinfunction "1_1") (pintype "unspecified"))
      (node (ref "C25") (pin "2") (pinfunction "2_2") (pintype "input"))
      (node (ref "C5") (pin "1") (pinfunction "1_1") (pintype "unspecified"))
      (node (ref "C6") (pin "1") (pinfunction "1_1") (pintype "unspecified"))
      (node (ref "C7") (pin "1") (pinfunction "1_1") (pintype "unspecified"))
      (node (ref "C8") (pin "1") (pinfunction "1_1") (pintype "unspecified"))
      (node (ref "C9") (pin "1") (pinfunction "1_1") (pintype "unspecified"))
      (node (ref "D2") (pin "2") (pinfunction "A_2") (pintype "unspecified"))
      (node (ref "D3") (pin "2") (pinfunction "A_2") (pintype "unspecified"))
      (node (ref "D4") (pin "1") (pinfunction "A_1") (pintype "unspecified"))
      (node (ref "D5") (pin "2") (pinfunction "A_2") (pintype "unspecified"))
      (node (ref "DM") (pin "3") (pinfunction "3_3") (pintype "unspecified"))
      (node (ref "DM") (pin "5") (pinfunction "5_5") (pintype "unspecified"))
      (node (ref "FB1") (pin "2") (pinfunction "2_2") (pintype "unspecified"))
      (node (ref "FB3") (pin "2") (pinfunction "2_2") (pintype "unspecified"))
      (node (ref "POWER") (pin "2") (pinfunction "2_2") (pintype "unspecified"))
      (node (ref "Q1") (pin "5") (pinfunction "S1_5") (pintype "unspecified"))
      (node (ref "R5") (pin "2") (pinfunction "2_2") (pintype "unspecified"))
      (node (ref "R6") (pin "2") (pinfunction "2_2") (pintype "unspecified"))
      (node (ref "RST") (pin "1") (pinfunction "1_1") (pintype "unspecified"))
      (node (ref "U1") (pin "145") (pinfunction "EP_145") (pintype "unspecified"))
      (node (ref "U1") (pin "80") (pinfunction "VSS_80") (pintype "unspecified"))
      (node (ref "U2") (pin "2") (pinfunction "GND_2") (pintype "unspecified"))
      (node (ref "Y2") (pin "2") (pinfunction "GND_2") (pintype "input"))
      (node (ref "Y2") (pin "4") (pinfunction "GND_4") (pintype "input"))
    )
    (net (code "132") (name "Net-(C20-Pad2)") (class "Default")
      (node (ref "C20") (pin "2") (pinfunction "2_2") (pintype "unspecified"))
      (node (ref "R3") (pin "1") (pinfunction "1_1") (pintype "unspecified"))
      (node (ref "R4") (pin "2") (pinfunction "2_2") (pintype "unspecified"))
      (node (ref "RST") (pin "2") (pinfunction "2_2") (pintype "unspecified"))
    )
    (net (code "133") (name "Net-(DM-Pad7)") (class "Default")
      (node (ref "DM") (pin "7") (pinfunction "7_7") (pintype "unspecified"))
      (node (ref "R14") (pin "2") (pinfunction "2_2") (pintype "unspecified"))
    )
    (net (code "134") (name "Net-(DM-Pad9)") (class "Default")
      (node (ref "DM") (pin "9") (pinfunction "9_9") (pintype "unspecified"))
      (node (ref "R15") (pin "2") (pinfunction "2_2") (pintype "unspecified"))
    )
    (net (code "135") (name "Net-(F1-Pad1)") (class "Default")
      (node (ref "F1") (pin "1") (pinfunction "1_1") (pintype "unspecified"))
      (node (ref "P1") (pin "1") (pinfunction "1_1") (pintype "unspecified"))
      (node (ref "P1") (pin "3") (pinfunction "3_3") (pintype "unspecified"))
    )
    (net (code "136") (name "Net-(FB3-Pad1)") (class "Default")
      (node (ref "FB3") (pin "1") (pinfunction "1_1") (pintype "unspecified"))
      (node (ref "P1") (pin "2") (pinfunction "2_2") (pintype "unspecified"))
      (node (ref "P1") (pin "4") (pinfunction "4_4") (pintype "unspecified"))
    )
    (net (code "137") (name "Net-(LED1-Pad1)") (class "Default")
      (node (ref "LED1") (pin "1") (pinfunction "1_1") (pintype "unspecified"))
      (node (ref "R17") (pin "2") (pinfunction "2_2") (pintype "unspecified"))
    )
    (net (code "138") (name "Net-(LED2-Pad1)") (class "Default")
      (node (ref "LED2") (pin "1") (pinfunction "1_1") (pintype "unspecified"))
      (node (ref "R18") (pin "2") (pinfunction "2_2") (pintype "unspecified"))
    )
    (net (code "139") (name "Net-(LED3-Pad1)") (class "Default")
      (node (ref "LED3") (pin "1") (pinfunction "1_1") (pintype "unspecified"))
      (node (ref "R19") (pin "2") (pinfunction "2_2") (pintype "unspecified"))
    )
    (net (code "140") (name "Net-(LED4-Pad1)") (class "Default")
      (node (ref "LED4") (pin "1") (pinfunction "1_1") (pintype "unspecified"))
      (node (ref "R20") (pin "2") (pinfunction "2_2") (pintype "unspecified"))
    )
    (net (code "141") (name "Net-(POWER-Pad1)") (class "Default")
      (node (ref "POWER") (pin "1") (pinfunction "1_1") (pintype "unspecified"))
      (node (ref "R16") (pin "2") (pinfunction "2_2") (pintype "unspecified"))
    )
    (net (code "142") (name "Net-(Q1-D1)") (class "Default")
      (node (ref "L1") (pin "1") (pinfunction "1_1") (pintype "unspecified"))
      (node (ref "Q1") (pin "4") (pinfunction "D2_4") (pintype "unspecified"))
      (node (ref "Q1") (pin "6") (pinfunction "D1_6") (pintype "unspecified"))
    )
    (net (code "143") (name "VCC") (class "Default")
      (node (ref "C23") (pin "2") (pinfunction "2_2") (pintype "unspecified"))
      (node (ref "C24") (pin "2") (pinfunction "2_2") (pintype "unspecified"))
      (node (ref "C25") (pin "1") (pinfunction "1_1") (pintype "input"))
      (node (ref "D1") (pin "1") (pinfunction "1_1") (pintype "unspecified"))
      (node (ref "D5") (pin "1") (pinfunction "C_1") (pintype "unspecified"))
      (node (ref "F1") (pin "2") (pinfunction "2_2") (pintype "unspecified"))
      (node (ref "U2") (pin "1") (pinfunction "VIN_1") (pintype "unspecified"))
      (node (ref "U2") (pin "3") (pinfunction "EN_3") (pintype "unspecified"))
    )
    (net (code "144") (name "VCC1V3") (class "Default")
      (node (ref "C11") (pin "2") (pinfunction "2_2") (pintype "unspecified"))
      (node (ref "C2") (pin "2") (pinfunction "2_2") (pintype "unspecified"))
      (node (ref "C5") (pin "2") (pinfunction "2_2") (pintype "unspecified"))
      (node (ref "C6") (pin "2") (pinfunction "2_2") (pintype "unspecified"))
      (node (ref "C7") (pin "2") (pinfunction "2_2") (pintype "unspecified"))
      (node (ref "C8") (pin "2") (pinfunction "2_2") (pintype "unspecified"))
      (node (ref "L1") (pin "2") (pinfunction "2_2") (pintype "unspecified"))
      (node (ref "U1") (pin "10") (pinfunction "VDD/VDDSB_10") (pintype "unspecified"))
      (node (ref "U1") (pin "22") (pinfunction "VDD_22") (pintype "unspecified"))
      (node (ref "U1") (pin "58") (pinfunction "VDD_58") (pintype "unspecified"))
      (node (ref "U1") (pin "79") (pinfunction "VDD_79") (pintype "unspecified"))
      (node (ref "U1") (pin "99") (pinfunction "VDD_99") (pintype "unspecified"))
    )
    (net (code "145") (name "VCC3V3") (class "Default")
      (node (ref "C1") (pin "2") (pinfunction "2_2") (pintype "unspecified"))
      (node (ref "C10") (pin "2") (pinfunction "2_2") (pintype "unspecified"))
      (node (ref "C12") (pin "2") (pinfunction "2_2") (pintype "unspecified"))
      (node (ref "C13") (pin "2") (pinfunction "2_2") (pintype "unspecified"))
      (node (ref "C14") (pin "2") (pinfunction "2_2") (pintype "unspecified"))
      (node (ref "C15") (pin "2") (pinfunction "2_2") (pintype "unspecified"))
      (node (ref "C16") (pin "2") (pinfunction "2_2") (pintype "unspecified"))
      (node (ref "C17") (pin "2") (pinfunction "2_2") (pintype "unspecified"))
      (node (ref "C21") (pin "1") (pinfunction "1_1") (pintype "unspecified"))
      (node (ref "C22") (pin "1") (pinfunction "1_1") (pintype "unspecified"))
      (node (ref "C9") (pin "2") (pinfunction "2_2") (pintype "unspecified"))
      (node (ref "D1") (pin "2") (pinfunction "2_2") (pintype "unspecified"))
      (node (ref "D2") (pin "1") (pinfunction "K_1") (pintype "unspecified"))
      (node (ref "D3") (pin "1") (pinfunction "K_1") (pintype "unspecified"))
      (node (ref "D4") (pin "2") (pinfunction "K_2") (pintype "unspecified"))
      (node (ref "DM") (pin "1") (pinfunction "1_1") (pintype "unspecified"))
      (node (ref "FB2") (pin "1") (pinfunction "1_1") (pintype "unspecified"))
      (node (ref "Q1") (pin "2") (pinfunction "S2_2") (pintype "unspecified"))
      (node (ref "R10") (pin "2") (pinfunction "2_2") (pintype "unspecified"))
      (node (ref "R11") (pin "2") (pinfunction "2_2") (pintype "unspecified"))
      (node (ref "R12") (pin "2") (pinfunction "2_2") (pintype "unspecified"))
      (node (ref "R13") (pin "2") (pinfunction "2_2") (pintype "unspecified"))
      (node (ref "R16") (pin "1") (pinfunction "1_1") (pintype "unspecified"))
      (node (ref "R17") (pin "1") (pinfunction "1_1") (pintype "unspecified"))
      (node (ref "R18") (pin "1") (pinfunction "1_1") (pintype "unspecified"))
      (node (ref "R19") (pin "1") (pinfunction "1_1") (pintype "unspecified"))
      (node (ref "R20") (pin "1") (pinfunction "1_1") (pintype "unspecified"))
      (node (ref "R4") (pin "1") (pinfunction "1_1") (pintype "unspecified"))
      (node (ref "R7") (pin "2") (pinfunction "2_2") (pintype "unspecified"))
      (node (ref "R8") (pin "2") (pinfunction "2_2") (pintype "unspecified"))
      (node (ref "R9") (pin "2") (pinfunction "2_2") (pintype "unspecified"))
      (node (ref "U1") (pin "125") (pinfunction "VEXT_125") (pintype "unspecified"))
      (node (ref "U1") (pin "126") (pinfunction "VDDP3_126") (pintype "unspecified"))
      (node (ref "U1") (pin "127") (pinfunction "VDDFL3_127") (pintype "unspecified"))
      (node (ref "U1") (pin "136") (pinfunction "VFLEX_136") (pintype "unspecified"))
      (node (ref "U1") (pin "23") (pinfunction "VEXT_23") (pintype "unspecified"))
      (node (ref "U1") (pin "59") (pinfunction "VEXT_59") (pintype "unspecified"))
      (node (ref "U1") (pin "78") (pinfunction "VEXT_78") (pintype "unspecified"))
      (node (ref "U1") (pin "83") (pinfunction "VDDP3_83") (pintype "unspecified"))
      (node (ref "U2") (pin "5") (pinfunction "VOUT_5") (pintype "unspecified"))
    )
    (net (code "146") (name "unconnected-(U2-NC-Pad4)") (class "Default")
      (node (ref "U2") (pin "4") (pinfunction "NC_4") (pintype "unspecified+no_connect"))
    )
  )
)
